# RapideUSBII.net
KiCad netlist of a schematic drawn in EAGLE
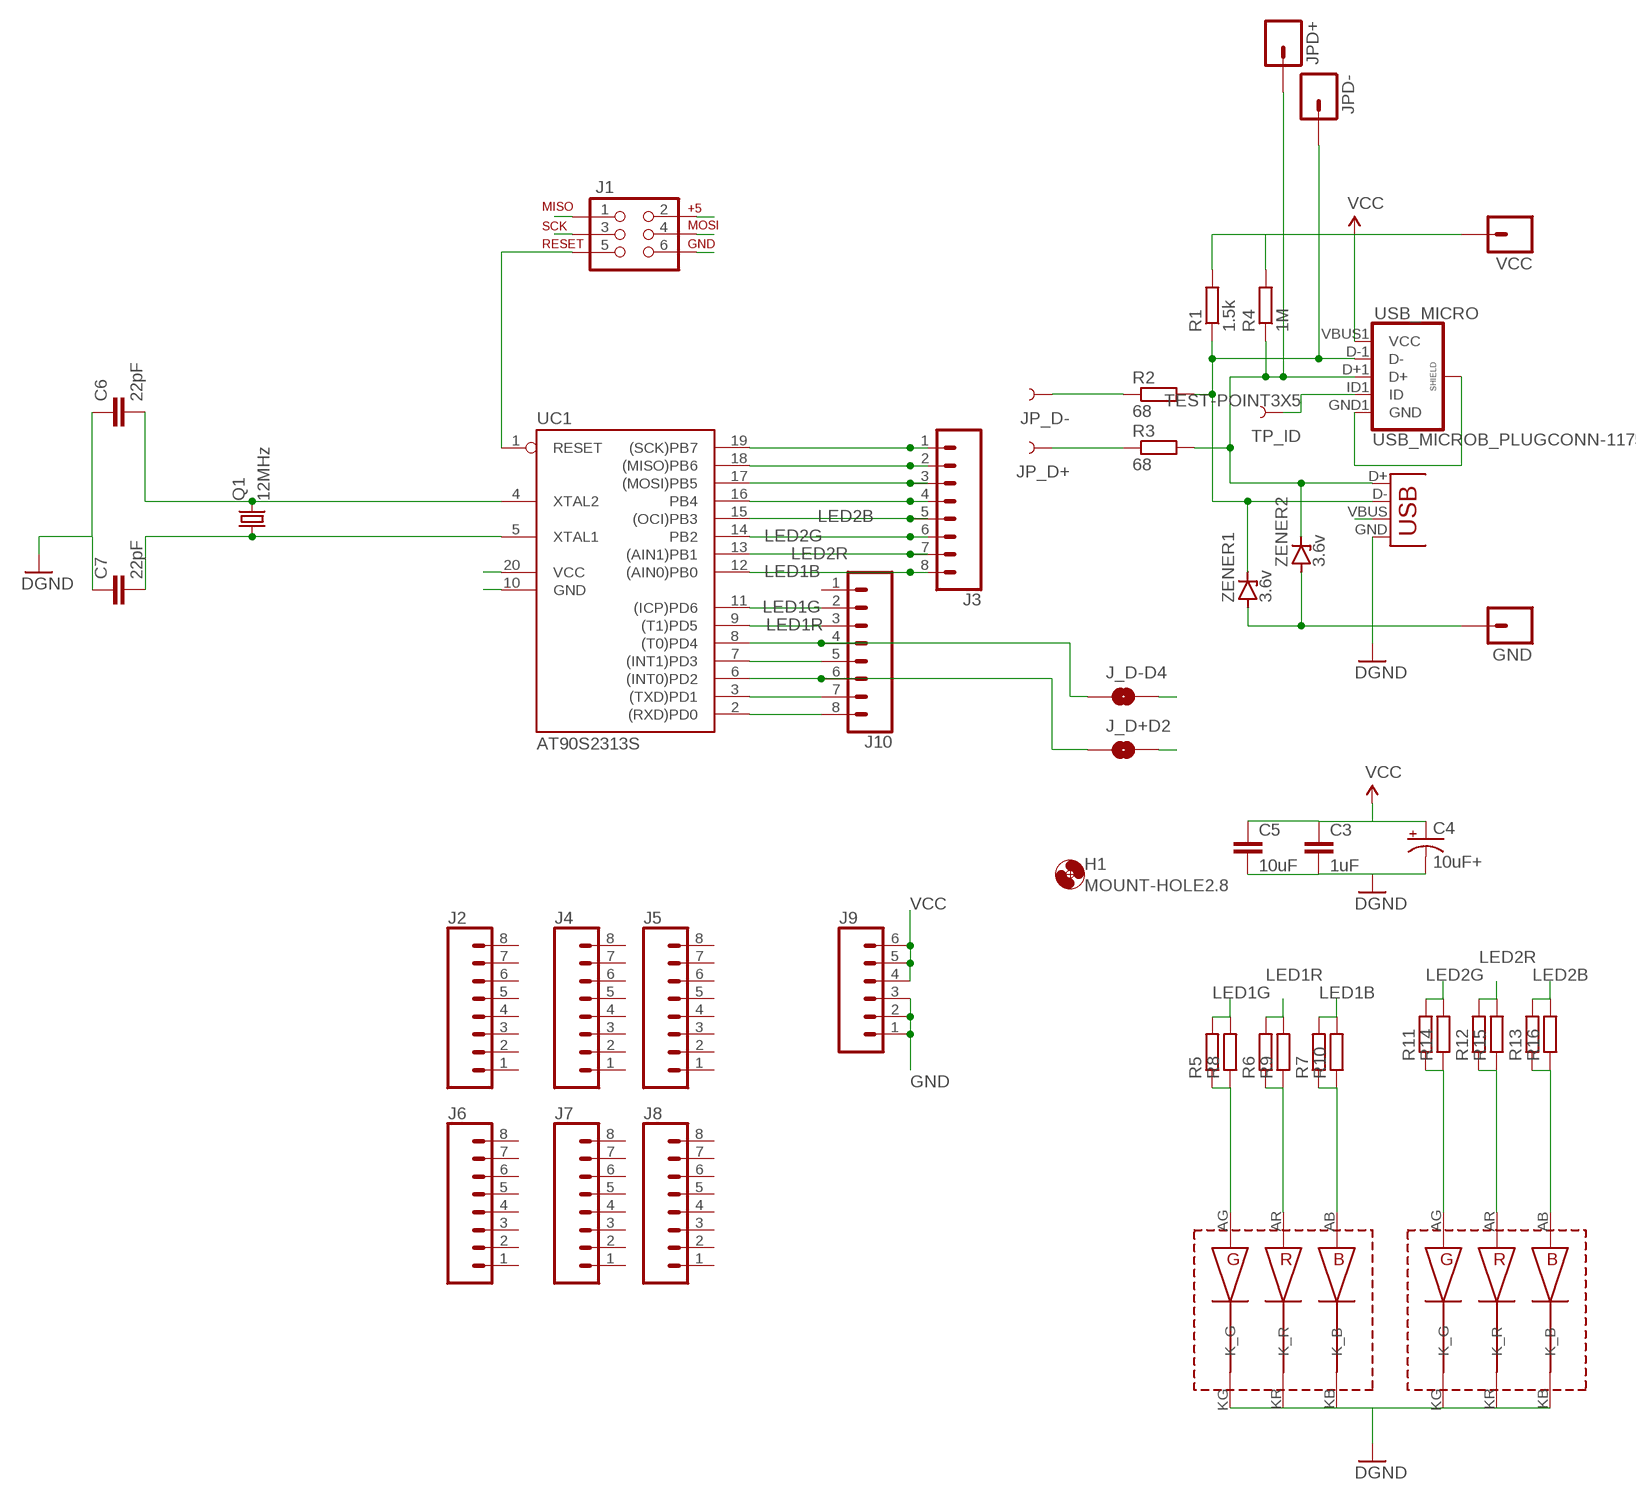
[diagram p0: schematic, sheet 1]

(export (version "E")
  (design (tool "Eeschema 10.0.6"))
  (components
    (comp (ref "C3")
      (value "1uF")
      (footprint "eagle-import:1206")
      (libsource (lib "eagle-import") (part "CAP1206"))
    )
    (comp (ref "C4")
      (value "10uF+")
      (footprint "eagle-import:PANASONIC_E")
      (libsource (lib "eagle-import") (part "CAP_POLE"))
    )
    (comp (ref "C5")
      (value "10uF")
      (footprint "eagle-import:0805")
      (libsource (lib "eagle-import") (part "CAP0805"))
    )
    (comp (ref "C6")
      (value "22pF")
      (footprint "eagle-import:1206")
      (libsource (lib "eagle-import") (part "CAP1206"))
    )
    (comp (ref "C7")
      (value "22pF")
      (footprint "eagle-import:1206")
      (libsource (lib "eagle-import") (part "CAP1206"))
    )
    (comp (ref "GND")
      (value "M01PTH_NO_SILK_YES_STOP")
      (footprint "eagle-import:1X01_NO_SILK")
      (libsource (lib "eagle-import") (part "M01PTH_NO_SILK_YES_STOP"))
    )
    (comp (ref "H1")
      (value "MOUNT-HOLE2.8")
      (footprint "eagle-import:2,8")
      (libsource (lib "eagle-import") (part "MOUNT-HOLE2.8"))
    )
    (comp (ref "J1")
      (value "AVR_SPI_PRG_6PTH")
      (footprint "eagle-import:2X3")
      (libsource (lib "eagle-import") (part "AVR_SPI_PRG_6PTH"))
    )
    (comp (ref "J2")
      (value "CONN_08NO_SILK_FEMALE_PTH")
      (footprint "eagle-import:1X08_NO_SILK")
      (libsource (lib "eagle-import") (part "CONN_08NO_SILK_FEMALE_PTH"))
    )
    (comp (ref "J3")
      (value "CONN_08SMD-STRAIGHT-ALT-FEMALE")
      (footprint "eagle-import:1X08_SMD_ALT")
      (libsource (lib "eagle-import") (part "CONN_08SMD-STRAIGHT-ALT-FEMALE"))
    )
    (comp (ref "J4")
      (value "CONN_08NO_SILK_FEMALE_PTH")
      (footprint "eagle-import:1X08_NO_SILK")
      (libsource (lib "eagle-import") (part "CONN_08NO_SILK_FEMALE_PTH"))
    )
    (comp (ref "J5")
      (value "CONN_08NO_SILK_FEMALE_PTH")
      (footprint "eagle-import:1X08_NO_SILK")
      (libsource (lib "eagle-import") (part "CONN_08NO_SILK_FEMALE_PTH"))
    )
    (comp (ref "J6")
      (value "CONN_08NO_SILK_FEMALE_PTH")
      (footprint "eagle-import:1X08_NO_SILK")
      (libsource (lib "eagle-import") (part "CONN_08NO_SILK_FEMALE_PTH"))
    )
    (comp (ref "J7")
      (value "CONN_08NO_SILK_FEMALE_PTH")
      (footprint "eagle-import:1X08_NO_SILK")
      (libsource (lib "eagle-import") (part "CONN_08NO_SILK_FEMALE_PTH"))
    )
    (comp (ref "J8")
      (value "CONN_08NO_SILK_FEMALE_PTH")
      (footprint "eagle-import:1X08_NO_SILK")
      (libsource (lib "eagle-import") (part "CONN_08NO_SILK_FEMALE_PTH"))
    )
    (comp (ref "J9")
      (value "CONN_06NO_SILK_FEMALE_PTH")
      (footprint "eagle-import:1X06_NO_SILK")
      (libsource (lib "eagle-import") (part "CONN_06NO_SILK_FEMALE_PTH"))
    )
    (comp (ref "J10")
      (value "CONN_08SMD-STRAIGHT-FEMALE")
      (footprint "eagle-import:1X08_SMD")
      (libsource (lib "eagle-import") (part "CONN_08SMD-STRAIGHT-FEMALE"))
    )
    (comp (ref "JPD+")
      (value "M01PTH_NO_SILK_YES_STOP")
      (footprint "eagle-import:1X01_NO_SILK")
      (libsource (lib "eagle-import") (part "M01PTH_NO_SILK_YES_STOP"))
    )
    (comp (ref "JPD-")
      (value "M01PTH_NO_SILK_YES_STOP")
      (footprint "eagle-import:1X01_NO_SILK")
      (libsource (lib "eagle-import") (part "M01PTH_NO_SILK_YES_STOP"))
    )
    (comp (ref "JP_D+")
      (value "TEST-POINT3X5")
      (footprint "eagle-import:PAD.03X.05")
      (libsource (lib "eagle-import") (part "SparkFun-Passives_TEST-POINT3X5"))
    )
    (comp (ref "JP_D-")
      (value "TEST-POINT3X5")
      (footprint "eagle-import:PAD.03X.05")
      (libsource (lib "eagle-import") (part "SparkFun-Passives_TEST-POINT3X5"))
    )
    (comp (ref "J_D+D2")
      (value "JUMPER-PAD-2-NOYES_SILK")
      (footprint "eagle-import:PAD-JUMPER-2-NO_YES_SILK")
      (libsource (lib "eagle-import") (part "JUMPER-PAD-2-NOYES_SILK"))
    )
    (comp (ref "J_D-D4")
      (value "JUMPER-PAD-2-NOYES_SILK")
      (footprint "eagle-import:PAD-JUMPER-2-NO_YES_SILK")
      (libsource (lib "eagle-import") (part "JUMPER-PAD-2-NOYES_SILK"))
    )
    (comp (ref "LED1")
      (value "RGB-SMT-SQUARE6X6MM")
      (footprint "eagle-import:SMT-SQUARE6")
      (libsource (lib "eagle-import") (part "RGB-SMT-SQUARE6X6MM"))
    )
    (comp (ref "LED2")
      (value "RGB-SMT-SQUARE5X5MM")
      (footprint "eagle-import:SMT-SQUARE5")
      (libsource (lib "eagle-import") (part "RGB-SMT-SQUARE5X5MM"))
    )
    (comp (ref "Q1")
      (value "12MHz")
      (footprint "eagle-import:HC49U")
      (libsource (lib "eagle-import") (part "CRYSTALPTH-HC49UV"))
    )
    (comp (ref "R1")
      (value "1.5k")
      (footprint "eagle-import:0204V")
      (libsource (lib "eagle-import") (part "R-EU_0204/2V"))
    )
    (comp (ref "R2")
      (value "68")
      (footprint "eagle-import:0204V")
      (libsource (lib "eagle-import") (part "R-EU_0204/2V"))
    )
    (comp (ref "R3")
      (value "68")
      (footprint "eagle-import:0204V")
      (libsource (lib "eagle-import") (part "R-EU_0204/2V"))
    )
    (comp (ref "R4")
      (value "1M")
      (footprint "eagle-import:0204V")
      (libsource (lib "eagle-import") (part "R-EU_0204/2V"))
    )
    (comp (ref "R5")
      (value "R-EU_0204/2V")
      (footprint "eagle-import:0204V")
      (libsource (lib "eagle-import") (part "R-EU_0204/2V"))
    )
    (comp (ref "R6")
      (value "R-EU_0204/2V")
      (footprint "eagle-import:0204V")
      (libsource (lib "eagle-import") (part "R-EU_0204/2V"))
    )
    (comp (ref "R7")
      (value "R-EU_0204/2V")
      (footprint "eagle-import:0204V")
      (libsource (lib "eagle-import") (part "R-EU_0204/2V"))
    )
    (comp (ref "R8")
      (value "R-EU_M1206")
      (footprint "eagle-import:M1206")
      (libsource (lib "eagle-import") (part "R-EU_M1206"))
    )
    (comp (ref "R9")
      (value "R-EU_M1206")
      (footprint "eagle-import:M1206")
      (libsource (lib "eagle-import") (part "R-EU_M1206"))
    )
    (comp (ref "R10")
      (value "R-EU_M1206")
      (footprint "eagle-import:M1206")
      (libsource (lib "eagle-import") (part "R-EU_M1206"))
    )
    (comp (ref "R11")
      (value "R-EU_0204/2V")
      (footprint "eagle-import:0204V")
      (libsource (lib "eagle-import") (part "R-EU_0204/2V"))
    )
    (comp (ref "R12")
      (value "R-EU_0204/2V")
      (footprint "eagle-import:0204V")
      (libsource (lib "eagle-import") (part "R-EU_0204/2V"))
    )
    (comp (ref "R13")
      (value "R-EU_0204/2V")
      (footprint "eagle-import:0204V")
      (libsource (lib "eagle-import") (part "R-EU_0204/2V"))
    )
    (comp (ref "R14")
      (value "R-EU_M1206")
      (footprint "eagle-import:M1206")
      (libsource (lib "eagle-import") (part "R-EU_M1206"))
    )
    (comp (ref "R15")
      (value "R-EU_M1206")
      (footprint "eagle-import:M1206")
      (libsource (lib "eagle-import") (part "R-EU_M1206"))
    )
    (comp (ref "R16")
      (value "R-EU_M1206")
      (footprint "eagle-import:M1206")
      (libsource (lib "eagle-import") (part "R-EU_M1206"))
    )
    (comp (ref "TP_ID")
      (value "TEST-POINT3X5")
      (footprint "eagle-import:PAD.03X.05")
      (libsource (lib "eagle-import") (part "TEST-POINT3X5"))
    )
    (comp (ref "UC1")
      (value "AT90S2313S")
      (footprint "eagle-import:SO20L")
      (libsource (lib "eagle-import") (part "AT90S2313S"))
    )
    (comp (ref "USB_MICRO")
      (value "USB_MICROB_PLUGCONN-11752")
      (footprint "eagle-import:USB-B-MICRO-SMD_V03")
      (libsource (lib "eagle-import") (part "USB_MICROB_PLUGCONN-11752"))
    )
    (comp (ref "USB_MINI")
      (value "USBSMD")
      (footprint "eagle-import:USB-MINIB")
      (libsource (lib "eagle-import") (part "USBSMD"))
    )
    (comp (ref "VCC")
      (value "M01PTH_NO_SILK_YES_STOP")
      (footprint "eagle-import:1X01_NO_SILK")
      (libsource (lib "eagle-import") (part "M01PTH_NO_SILK_YES_STOP"))
    )
    (comp (ref "ZENER1")
      (value "3.6v")
      (footprint "eagle-import:ZDIO-2.5")
      (libsource (lib "eagle-import") (part "ZENER-DIODEZD-2.5"))
    )
    (comp (ref "ZENER2")
      (value "3.6v")
      (footprint "eagle-import:ZDIO-2.5")
      (libsource (lib "eagle-import") (part "ZENER-DIODEZD-2.5"))
    )
  )
  (nets
    (net (code "1") (name "/D+") (class "Default")
      (node (ref "JP_D+") (pin "P$1") (pinfunction "1_P$1") (pintype "bidirectional"))
      (node (ref "J_D+D2") (pin "2") (pinfunction "2_2") (pintype "passive"))
      (node (ref "R3") (pin "1") (pinfunction "1_1") (pintype "passive"))
    )
    (net (code "2") (name "/D-") (class "Default")
      (node (ref "JP_D-") (pin "P$1") (pinfunction "1_P$1") (pintype "bidirectional"))
      (node (ref "J_D-D4") (pin "2") (pinfunction "2_2") (pintype "passive"))
      (node (ref "R2") (pin "1") (pinfunction "1_1") (pintype "passive"))
    )
    (net (code "3") (name "/LED1B") (class "Default")
      (node (ref "J3") (pin "8") (pinfunction "8_8") (pintype "passive"))
      (node (ref "R10") (pin "2") (pinfunction "2_2") (pintype "passive"))
      (node (ref "R7") (pin "2") (pinfunction "2_2") (pintype "passive"))
      (node (ref "UC1") (pin "12") (pinfunction "(AIN0)PB0_12") (pintype "bidirectional"))
    )
    (net (code "4") (name "/LED1G") (class "Default")
      (node (ref "J10") (pin "2") (pinfunction "2_2") (pintype "passive"))
      (node (ref "R5") (pin "2") (pinfunction "2_2") (pintype "passive"))
      (node (ref "R8") (pin "2") (pinfunction "2_2") (pintype "passive"))
      (node (ref "UC1") (pin "11") (pinfunction "(ICP)PD6_11") (pintype "bidirectional"))
    )
    (net (code "5") (name "/LED1R") (class "Default")
      (node (ref "J10") (pin "3") (pinfunction "3_3") (pintype "passive"))
      (node (ref "R6") (pin "2") (pinfunction "2_2") (pintype "passive"))
      (node (ref "R9") (pin "2") (pinfunction "2_2") (pintype "passive"))
      (node (ref "UC1") (pin "9") (pinfunction "(T1)PD5_9") (pintype "bidirectional"))
    )
    (net (code "6") (name "/LED2B") (class "Default")
      (node (ref "J3") (pin "5") (pinfunction "5_5") (pintype "passive"))
      (node (ref "R13") (pin "2") (pinfunction "2_2") (pintype "passive"))
      (node (ref "R16") (pin "2") (pinfunction "2_2") (pintype "passive"))
      (node (ref "UC1") (pin "15") (pinfunction "(OCI)PB3_15") (pintype "bidirectional"))
    )
    (net (code "7") (name "/LED2G") (class "Default")
      (node (ref "J3") (pin "6") (pinfunction "6_6") (pintype "passive"))
      (node (ref "R11") (pin "2") (pinfunction "2_2") (pintype "passive"))
      (node (ref "R14") (pin "2") (pinfunction "2_2") (pintype "passive"))
      (node (ref "UC1") (pin "14") (pinfunction "PB2_14") (pintype "bidirectional"))
    )
    (net (code "8") (name "/LED2R") (class "Default")
      (node (ref "J3") (pin "7") (pinfunction "7_7") (pintype "passive"))
      (node (ref "R12") (pin "2") (pinfunction "2_2") (pintype "passive"))
      (node (ref "R15") (pin "2") (pinfunction "2_2") (pintype "passive"))
      (node (ref "UC1") (pin "13") (pinfunction "(AIN1)PB1_13") (pintype "bidirectional"))
    )
    (net (code "9") (name "/MISO") (class "Default")
      (node (ref "J1") (pin "1") (pinfunction "1_1") (pintype "passive"))
      (node (ref "J3") (pin "2") (pinfunction "2_2") (pintype "passive"))
      (node (ref "UC1") (pin "18") (pinfunction "(MISO)PB6_18") (pintype "bidirectional"))
    )
    (net (code "10") (name "/MOSI") (class "Default")
      (node (ref "J1") (pin "4") (pinfunction "4_4") (pintype "passive"))
      (node (ref "J3") (pin "3") (pinfunction "3_3") (pintype "passive"))
      (node (ref "UC1") (pin "17") (pinfunction "(MOSI)PB5_17") (pintype "bidirectional"))
    )
    (net (code "11") (name "/SCK") (class "Default")
      (node (ref "J1") (pin "3") (pinfunction "3_3") (pintype "passive"))
      (node (ref "J3") (pin "1") (pinfunction "1_1") (pintype "passive"))
      (node (ref "UC1") (pin "19") (pinfunction "(SCK)PB7_19") (pintype "bidirectional"))
    )
    (net (code "12") (name "DGND") (class "Default")
      (node (ref "C3") (pin "2") (pinfunction "2_2") (pintype "passive"))
      (node (ref "C4") (pin "-") (pinfunction "-_-") (pintype "passive"))
      (node (ref "C5") (pin "2") (pinfunction "2_2") (pintype "passive"))
      (node (ref "C6") (pin "1") (pinfunction "1_1") (pintype "passive"))
      (node (ref "C7") (pin "1") (pinfunction "1_1") (pintype "passive"))
      (node (ref "GND") (pin "1") (pinfunction "1_1") (pintype "passive"))
      (node (ref "J1") (pin "6") (pinfunction "6_6") (pintype "passive"))
      (node (ref "J9") (pin "1") (pinfunction "1_1") (pintype "passive"))
      (node (ref "J9") (pin "2") (pinfunction "2_2") (pintype "passive"))
      (node (ref "J9") (pin "3") (pinfunction "3_3") (pintype "passive"))
      (node (ref "LED1") (pin "KB") (pinfunction "K_B_KB") (pintype "bidirectional"))
      (node (ref "LED1") (pin "KG") (pinfunction "K_G_KG") (pintype "bidirectional"))
      (node (ref "LED1") (pin "KR") (pinfunction "K_R_KR") (pintype "bidirectional"))
      (node (ref "LED2") (pin "KB") (pinfunction "K_B_KB") (pintype "bidirectional"))
      (node (ref "LED2") (pin "KG") (pinfunction "K_G_KG") (pintype "bidirectional"))
      (node (ref "LED2") (pin "KR") (pinfunction "K_R_KR") (pintype "bidirectional"))
      (node (ref "UC1") (pin "10") (pinfunction "GND_10") (pintype "power_in"))
      (node (ref "USB_MICRO") (pin "GND1") (pinfunction "GND_GND1") (pintype "bidirectional"))
      (node (ref "USB_MICRO") (pin "SHIELD1") (pinfunction "SHIELD_SHIELD1") (pintype "bidirectional"))
      (node (ref "USB_MICRO") (pin "SHIELD2") (pinfunction "SHIELD_SHIELD2") (pintype "bidirectional"))
      (node (ref "USB_MICRO") (pin "SHIELD3") (pinfunction "SHIELD_SHIELD3") (pintype "bidirectional"))
      (node (ref "USB_MINI") (pin "GND") (pinfunction "GND_GND") (pintype "bidirectional"))
      (node (ref "ZENER1") (pin "A") (pinfunction "A_A") (pintype "passive"))
      (node (ref "ZENER2") (pin "A") (pinfunction "A_A") (pintype "passive"))
    )
    (net (code "13") (name "Net-(LED1-ANODE_B)") (class "Default")
      (node (ref "LED1") (pin "AB") (pinfunction "ANODE_B_AB") (pintype "bidirectional"))
      (node (ref "R10") (pin "1") (pinfunction "1_1") (pintype "passive"))
      (node (ref "R7") (pin "1") (pinfunction "1_1") (pintype "passive"))
    )
    (net (code "14") (name "Net-(LED1-ANODE_G)") (class "Default")
      (node (ref "LED1") (pin "AG") (pinfunction "ANODE_G_AG") (pintype "bidirectional"))
      (node (ref "R5") (pin "1") (pinfunction "1_1") (pintype "passive"))
      (node (ref "R8") (pin "1") (pinfunction "1_1") (pintype "passive"))
    )
    (net (code "15") (name "Net-(LED1-ANODE_R)") (class "Default")
      (node (ref "LED1") (pin "AR") (pinfunction "ANODE_R_AR") (pintype "bidirectional"))
      (node (ref "R6") (pin "1") (pinfunction "1_1") (pintype "passive"))
      (node (ref "R9") (pin "1") (pinfunction "1_1") (pintype "passive"))
    )
    (net (code "16") (name "Net-(LED2-ANODE_B)") (class "Default")
      (node (ref "LED2") (pin "AB") (pinfunction "ANODE_B_AB") (pintype "bidirectional"))
      (node (ref "R13") (pin "1") (pinfunction "1_1") (pintype "passive"))
      (node (ref "R16") (pin "1") (pinfunction "1_1") (pintype "passive"))
    )
    (net (code "17") (name "Net-(LED2-ANODE_G)") (class "Default")
      (node (ref "LED2") (pin "AG") (pinfunction "ANODE_G_AG") (pintype "bidirectional"))
      (node (ref "R11") (pin "1") (pinfunction "1_1") (pintype "passive"))
      (node (ref "R14") (pin "1") (pinfunction "1_1") (pintype "passive"))
    )
    (net (code "18") (name "Net-(LED2-ANODE_R)") (class "Default")
      (node (ref "LED2") (pin "AR") (pinfunction "ANODE_R_AR") (pintype "bidirectional"))
      (node (ref "R12") (pin "1") (pinfunction "1_1") (pintype "passive"))
      (node (ref "R15") (pin "1") (pinfunction "1_1") (pintype "passive"))
    )
    (net (code "19") (name "Net-(TP_ID-1)") (class "Default")
      (node (ref "TP_ID") (pin "P$1") (pinfunction "1_P$1") (pintype "bidirectional"))
      (node (ref "USB_MICRO") (pin "ID1") (pinfunction "ID_ID1") (pintype "bidirectional"))
    )
    (net (code "20") (name "Net-(UC1-(INT0)PD2)") (class "Default")
      (node (ref "J10") (pin "6") (pinfunction "6_6") (pintype "passive"))
      (node (ref "J_D+D2") (pin "1") (pinfunction "1_1") (pintype "passive"))
      (node (ref "UC1") (pin "6") (pinfunction "(INT0)PD2_6") (pintype "bidirectional"))
    )
    (net (code "21") (name "Net-(UC1-(INT1)PD3)") (class "Default")
      (node (ref "J10") (pin "5") (pinfunction "5_5") (pintype "passive"))
      (node (ref "UC1") (pin "7") (pinfunction "(INT1)PD3_7") (pintype "bidirectional"))
    )
    (net (code "22") (name "Net-(UC1-(RXD)PD0)") (class "Default")
      (node (ref "J10") (pin "8") (pinfunction "8_8") (pintype "passive"))
      (node (ref "UC1") (pin "2") (pinfunction "(RXD)PD0_2") (pintype "bidirectional"))
    )
    (net (code "23") (name "Net-(UC1-(T0)PD4)") (class "Default")
      (node (ref "J10") (pin "4") (pinfunction "4_4") (pintype "passive"))
      (node (ref "J_D-D4") (pin "1") (pinfunction "1_1") (pintype "passive"))
      (node (ref "UC1") (pin "8") (pinfunction "(T0)PD4_8") (pintype "bidirectional"))
    )
    (net (code "24") (name "Net-(UC1-(TXD)PD1)") (class "Default")
      (node (ref "J10") (pin "7") (pinfunction "7_7") (pintype "passive"))
      (node (ref "UC1") (pin "3") (pinfunction "(TXD)PD1_3") (pintype "bidirectional"))
    )
    (net (code "25") (name "Net-(UC1-PB4)") (class "Default")
      (node (ref "J3") (pin "4") (pinfunction "4_4") (pintype "passive"))
      (node (ref "UC1") (pin "16") (pinfunction "PB4_16") (pintype "bidirectional"))
    )
    (net (code "26") (name "Net-(UC1-RESET)") (class "Default")
      (node (ref "J1") (pin "5") (pinfunction "5_5") (pintype "passive"))
      (node (ref "UC1") (pin "1") (pinfunction "RESET_1") (pintype "bidirectional"))
    )
    (net (code "27") (name "Net-(UC1-XTAL1)") (class "Default")
      (node (ref "C7") (pin "2") (pinfunction "2_2") (pintype "passive"))
      (node (ref "Q1") (pin "1") (pinfunction "1_1") (pintype "passive"))
      (node (ref "UC1") (pin "5") (pinfunction "XTAL1_5") (pintype "bidirectional"))
    )
    (net (code "28") (name "Net-(UC1-XTAL2)") (class "Default")
      (node (ref "C6") (pin "2") (pinfunction "2_2") (pintype "passive"))
      (node (ref "Q1") (pin "2") (pinfunction "2_2") (pintype "passive"))
      (node (ref "UC1") (pin "4") (pinfunction "XTAL2_4") (pintype "bidirectional"))
    )
    (net (code "29") (name "Net-(USB_MICRO-D+)") (class "Default")
      (node (ref "JPD+") (pin "1") (pinfunction "1_1") (pintype "passive"))
      (node (ref "R3") (pin "2") (pinfunction "2_2") (pintype "passive"))
      (node (ref "R4") (pin "1") (pinfunction "1_1") (pintype "passive"))
      (node (ref "USB_MICRO") (pin "D+1") (pinfunction "D+_D+1") (pintype "bidirectional"))
      (node (ref "USB_MINI") (pin "D+") (pinfunction "D+_D+") (pintype "bidirectional"))
      (node (ref "ZENER2") (pin "C") (pinfunction "C_C") (pintype "passive"))
    )
    (net (code "30") (name "Net-(USB_MICRO-D-)") (class "Default")
      (node (ref "JPD-") (pin "1") (pinfunction "1_1") (pintype "passive"))
      (node (ref "R1") (pin "1") (pinfunction "1_1") (pintype "passive"))
      (node (ref "R2") (pin "2") (pinfunction "2_2") (pintype "passive"))
      (node (ref "USB_MICRO") (pin "D-1") (pinfunction "D-_D-1") (pintype "bidirectional"))
      (node (ref "USB_MINI") (pin "D-") (pinfunction "D-_D-") (pintype "bidirectional"))
      (node (ref "ZENER1") (pin "C") (pinfunction "C_C") (pintype "passive"))
    )
    (net (code "31") (name "VCC") (class "Default")
      (node (ref "C3") (pin "1") (pinfunction "1_1") (pintype "passive"))
      (node (ref "C4") (pin "+") (pinfunction "+_+") (pintype "passive"))
      (node (ref "C5") (pin "1") (pinfunction "1_1") (pintype "passive"))
      (node (ref "J1") (pin "2") (pinfunction "2_2") (pintype "passive"))
      (node (ref "J9") (pin "4") (pinfunction "4_4") (pintype "passive"))
      (node (ref "J9") (pin "5") (pinfunction "5_5") (pintype "passive"))
      (node (ref "J9") (pin "6") (pinfunction "6_6") (pintype "passive"))
      (node (ref "R1") (pin "2") (pinfunction "2_2") (pintype "passive"))
      (node (ref "R4") (pin "2") (pinfunction "2_2") (pintype "passive"))
      (node (ref "UC1") (pin "20") (pinfunction "VCC_20") (pintype "power_in"))
      (node (ref "USB_MICRO") (pin "VBUS1") (pinfunction "VCC_VBUS1") (pintype "bidirectional"))
      (node (ref "USB_MINI") (pin "VBUS") (pinfunction "VBUS_VBUS") (pintype "bidirectional"))
      (node (ref "VCC") (pin "1") (pinfunction "1_1") (pintype "passive"))
    )
    (net (code "32") (name "unconnected-(J2-Pad1)") (class "Default")
      (node (ref "J2") (pin "1") (pinfunction "1_1") (pintype "passive"))
    )
    (net (code "33") (name "unconnected-(J2-Pad2)") (class "Default")
      (node (ref "J2") (pin "2") (pinfunction "2_2") (pintype "passive"))
    )
    (net (code "34") (name "unconnected-(J2-Pad3)") (class "Default")
      (node (ref "J2") (pin "3") (pinfunction "3_3") (pintype "passive"))
    )
    (net (code "35") (name "unconnected-(J2-Pad4)") (class "Default")
      (node (ref "J2") (pin "4") (pinfunction "4_4") (pintype "passive"))
    )
    (net (code "36") (name "unconnected-(J2-Pad5)") (class "Default")
      (node (ref "J2") (pin "5") (pinfunction "5_5") (pintype "passive"))
    )
    (net (code "37") (name "unconnected-(J2-Pad6)") (class "Default")
      (node (ref "J2") (pin "6") (pinfunction "6_6") (pintype "passive"))
    )
    (net (code "38") (name "unconnected-(J2-Pad7)") (class "Default")
      (node (ref "J2") (pin "7") (pinfunction "7_7") (pintype "passive"))
    )
    (net (code "39") (name "unconnected-(J2-Pad8)") (class "Default")
      (node (ref "J2") (pin "8") (pinfunction "8_8") (pintype "passive"))
    )
    (net (code "40") (name "unconnected-(J4-Pad1)") (class "Default")
      (node (ref "J4") (pin "1") (pinfunction "1_1") (pintype "passive"))
    )
    (net (code "41") (name "unconnected-(J4-Pad2)") (class "Default")
      (node (ref "J4") (pin "2") (pinfunction "2_2") (pintype "passive"))
    )
    (net (code "42") (name "unconnected-(J4-Pad3)") (class "Default")
      (node (ref "J4") (pin "3") (pinfunction "3_3") (pintype "passive"))
    )
    (net (code "43") (name "unconnected-(J4-Pad4)") (class "Default")
      (node (ref "J4") (pin "4") (pinfunction "4_4") (pintype "passive"))
    )
    (net (code "44") (name "unconnected-(J4-Pad5)") (class "Default")
      (node (ref "J4") (pin "5") (pinfunction "5_5") (pintype "passive"))
    )
    (net (code "45") (name "unconnected-(J4-Pad6)") (class "Default")
      (node (ref "J4") (pin "6") (pinfunction "6_6") (pintype "passive"))
    )
    (net (code "46") (name "unconnected-(J4-Pad7)") (class "Default")
      (node (ref "J4") (pin "7") (pinfunction "7_7") (pintype "passive"))
    )
    (net (code "47") (name "unconnected-(J4-Pad8)") (class "Default")
      (node (ref "J4") (pin "8") (pinfunction "8_8") (pintype "passive"))
    )
    (net (code "48") (name "unconnected-(J5-Pad1)") (class "Default")
      (node (ref "J5") (pin "1") (pinfunction "1_1") (pintype "passive"))
    )
    (net (code "49") (name "unconnected-(J5-Pad2)") (class "Default")
      (node (ref "J5") (pin "2") (pinfunction "2_2") (pintype "passive"))
    )
    (net (code "50") (name "unconnected-(J5-Pad3)") (class "Default")
      (node (ref "J5") (pin "3") (pinfunction "3_3") (pintype "passive"))
    )
    (net (code "51") (name "unconnected-(J5-Pad4)") (class "Default")
      (node (ref "J5") (pin "4") (pinfunction "4_4") (pintype "passive"))
    )
    (net (code "52") (name "unconnected-(J5-Pad5)") (class "Default")
      (node (ref "J5") (pin "5") (pinfunction "5_5") (pintype "passive"))
    )
    (net (code "53") (name "unconnected-(J5-Pad6)") (class "Default")
      (node (ref "J5") (pin "6") (pinfunction "6_6") (pintype "passive"))
    )
    (net (code "54") (name "unconnected-(J5-Pad7)") (class "Default")
      (node (ref "J5") (pin "7") (pinfunction "7_7") (pintype "passive"))
    )
    (net (code "55") (name "unconnected-(J5-Pad8)") (class "Default")
      (node (ref "J5") (pin "8") (pinfunction "8_8") (pintype "passive"))
    )
    (net (code "56") (name "unconnected-(J6-Pad1)") (class "Default")
      (node (ref "J6") (pin "1") (pinfunction "1_1") (pintype "passive"))
    )
    (net (code "57") (name "unconnected-(J6-Pad2)") (class "Default")
      (node (ref "J6") (pin "2") (pinfunction "2_2") (pintype "passive"))
    )
    (net (code "58") (name "unconnected-(J6-Pad3)") (class "Default")
      (node (ref "J6") (pin "3") (pinfunction "3_3") (pintype "passive"))
    )
    (net (code "59") (name "unconnected-(J6-Pad4)") (class "Default")
      (node (ref "J6") (pin "4") (pinfunction "4_4") (pintype "passive"))
    )
    (net (code "60") (name "unconnected-(J6-Pad5)") (class "Default")
      (node (ref "J6") (pin "5") (pinfunction "5_5") (pintype "passive"))
    )
    (net (code "61") (name "unconnected-(J6-Pad6)") (class "Default")
      (node (ref "J6") (pin "6") (pinfunction "6_6") (pintype "passive"))
    )
    (net (code "62") (name "unconnected-(J6-Pad7)") (class "Default")
      (node (ref "J6") (pin "7") (pinfunction "7_7") (pintype "passive"))
    )
    (net (code "63") (name "unconnected-(J6-Pad8)") (class "Default")
      (node (ref "J6") (pin "8") (pinfunction "8_8") (pintype "passive"))
    )
    (net (code "64") (name "unconnected-(J7-Pad1)") (class "Default")
      (node (ref "J7") (pin "1") (pinfunction "1_1") (pintype "passive"))
    )
    (net (code "65") (name "unconnected-(J7-Pad2)") (class "Default")
      (node (ref "J7") (pin "2") (pinfunction "2_2") (pintype "passive"))
    )
    (net (code "66") (name "unconnected-(J7-Pad3)") (class "Default")
      (node (ref "J7") (pin "3") (pinfunction "3_3") (pintype "passive"))
    )
    (net (code "67") (name "unconnected-(J7-Pad4)") (class "Default")
      (node (ref "J7") (pin "4") (pinfunction "4_4") (pintype "passive"))
    )
    (net (code "68") (name "unconnected-(J7-Pad5)") (class "Default")
      (node (ref "J7") (pin "5") (pinfunction "5_5") (pintype "passive"))
    )
    (net (code "69") (name "unconnected-(J7-Pad6)") (class "Default")
      (node (ref "J7") (pin "6") (pinfunction "6_6") (pintype "passive"))
    )
    (net (code "70") (name "unconnected-(J7-Pad7)") (class "Default")
      (node (ref "J7") (pin "7") (pinfunction "7_7") (pintype "passive"))
    )
    (net (code "71") (name "unconnected-(J7-Pad8)") (class "Default")
      (node (ref "J7") (pin "8") (pinfunction "8_8") (pintype "passive"))
    )
    (net (code "72") (name "unconnected-(J8-Pad1)") (class "Default")
      (node (ref "J8") (pin "1") (pinfunction "1_1") (pintype "passive"))
    )
    (net (code "73") (name "unconnected-(J8-Pad2)") (class "Default")
      (node (ref "J8") (pin "2") (pinfunction "2_2") (pintype "passive"))
    )
    (net (code "74") (name "unconnected-(J8-Pad3)") (class "Default")
      (node (ref "J8") (pin "3") (pinfunction "3_3") (pintype "passive"))
    )
    (net (code "75") (name "unconnected-(J8-Pad4)") (class "Default")
      (node (ref "J8") (pin "4") (pinfunction "4_4") (pintype "passive"))
    )
    (net (code "76") (name "unconnected-(J8-Pad5)") (class "Default")
      (node (ref "J8") (pin "5") (pinfunction "5_5") (pintype "passive"))
    )
    (net (code "77") (name "unconnected-(J8-Pad6)") (class "Default")
      (node (ref "J8") (pin "6") (pinfunction "6_6") (pintype "passive"))
    )
    (net (code "78") (name "unconnected-(J8-Pad7)") (class "Default")
      (node (ref "J8") (pin "7") (pinfunction "7_7") (pintype "passive"))
    )
    (net (code "79") (name "unconnected-(J8-Pad8)") (class "Default")
      (node (ref "J8") (pin "8") (pinfunction "8_8") (pintype "passive"))
    )
    (net (code "80") (name "unconnected-(J10-Pad1)") (class "Default")
      (node (ref "J10") (pin "1") (pinfunction "1_1") (pintype "passive"))
    )
  )
)
